# G-PiC_Door_Controller.net
KiCad netlist of a schematic drawn in EAGLE
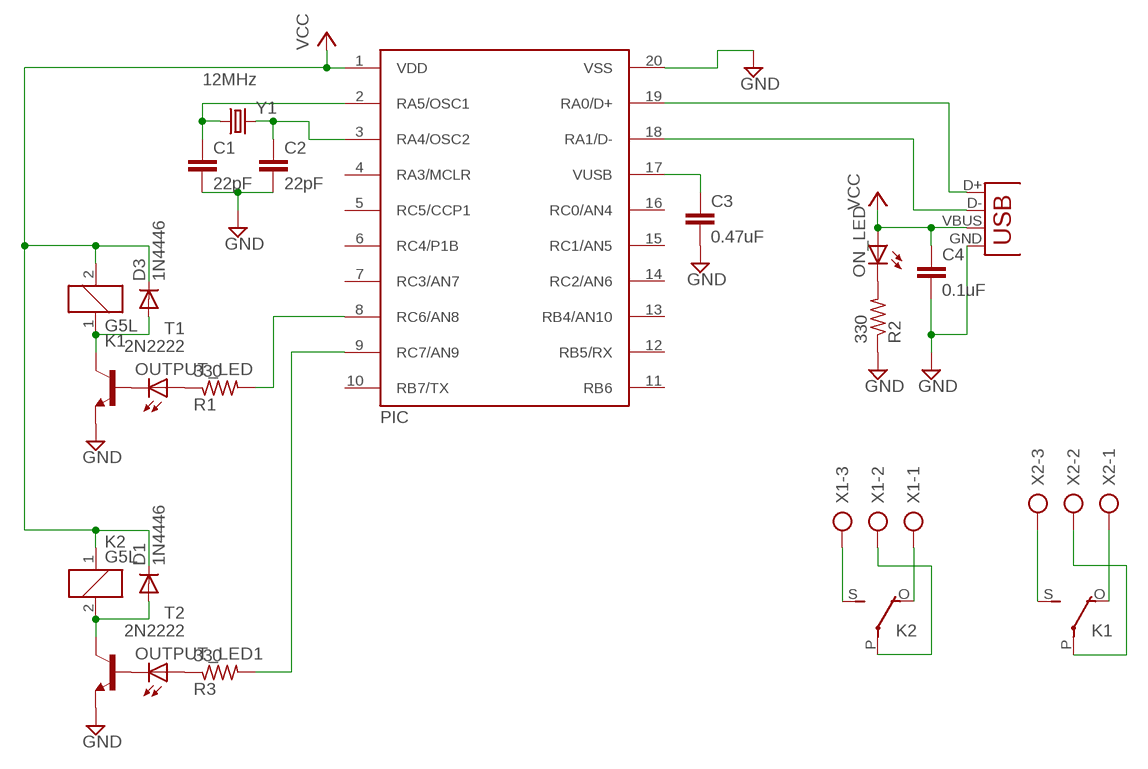
[diagram p0: schematic, sheet 1]

(export (version "E")
  (design (tool "Eeschema 10.0.6"))
  (components
    (comp (ref "C1")
      (value "22pF")
      (footprint "eagle-import:C5B3")
      (libsource (lib "eagle-import") (part "C5/3"))
    )
    (comp (ref "C2")
      (value "22pF")
      (footprint "eagle-import:C5B3")
      (libsource (lib "eagle-import") (part "C5/3"))
    )
    (comp (ref "C3")
      (value "0.47uF")
      (footprint "eagle-import:C5B3")
      (libsource (lib "eagle-import") (part "C5/3"))
    )
    (comp (ref "C4")
      (value "0.1uF")
      (footprint "eagle-import:C2.5-3")
      (libsource (lib "eagle-import") (part "C2,5-3"))
    )
    (comp (ref "D1")
      (value "1N4446")
      (footprint "eagle-import:DO35-10")
      (libsource (lib "eagle-import") (part "1N4446"))
    )
    (comp (ref "D3")
      (value "1N4446")
      (footprint "eagle-import:DO35-10")
      (libsource (lib "eagle-import") (part "1N4446"))
    )
    (comp (ref "K1")
      (value "G5L")
      (footprint "eagle-import:G5LE")
      (libsource (lib "eagle-import") (part "G5L"))
    )
    (comp (ref "K2")
      (value "G5L")
      (footprint "eagle-import:G5LE")
      (fields (field (name "OC_FARNELL") "unknown") (field (name "OC_NEWARK") "unknown"))
      (libsource (lib "eagle-import") (part "G5L"))
    )
    (comp (ref "ON_LED")
      (value "LED3MM")
      (footprint "eagle-import:LED3MM")
      (libsource (lib "eagle-import") (part "LED3MM"))
    )
    (comp (ref "OUTPUT_LED")
      (value "LED3MM")
      (footprint "eagle-import:LED3MM")
      (libsource (lib "eagle-import") (part "LED3MM"))
    )
    (comp (ref "OUTPUT_LED1")
      (value "LED3MM")
      (footprint "eagle-import:LED3MM")
      (libsource (lib "eagle-import") (part "LED3MM"))
    )
    (comp (ref "PIC")
      (value "PIC18F14K50")
      (footprint "eagle-import:DIL20")
      (libsource (lib "eagle-import") (part "PIC18F14K50"))
    )
    (comp (ref "R1")
      (value "330")
      (footprint "eagle-import:0204_7")
      (libsource (lib "eagle-import") (part "R-US_0204/7"))
    )
    (comp (ref "R2")
      (value "330")
      (footprint "eagle-import:0204_7")
      (libsource (lib "eagle-import") (part "R-US_0204/7"))
    )
    (comp (ref "R3")
      (value "330")
      (footprint "eagle-import:0204_7")
      (libsource (lib "eagle-import") (part "R-US_0204/7"))
    )
    (comp (ref "T1")
      (value "2N2222")
      (footprint "eagle-import:TO92-EBC-OVAL")
      (libsource (lib "eagle-import") (part "2N2222"))
    )
    (comp (ref "T2")
      (value "2N2222")
      (footprint "eagle-import:TO92-EBC-OVAL")
      (libsource (lib "eagle-import") (part "2N2222"))
    )
    (comp (ref "X1")
      (value "AK500/3-H")
      (footprint "eagle-import:AK500_3-H")
      (fields (field (name "OC_FARNELL") "unknown") (field (name "OC_NEWARK") "unknown"))
      (libsource (lib "eagle-import") (part "AK500/3-H"))
    )
    (comp (ref "X2")
      (value "AK500/3-H")
      (footprint "eagle-import:AK500_3-H")
      (libsource (lib "eagle-import") (part "AK500/3-H"))
    )
    (comp (ref "X3")
      (value "USBPTH")
      (footprint "eagle-import:USB-B-PTH")
      (libsource (lib "eagle-import") (part "USBPTH"))
    )
    (comp (ref "Y1")
      (value "12MHz")
      (footprint "eagle-import:HC49US")
      (libsource (lib "eagle-import") (part "CRYSTALHC49US"))
    )
  )
  (nets
    (net (code "1") (name "GND") (class "Default")
      (node (ref "C1") (pin "2") (pinfunction "2_2") (pintype "passive"))
      (node (ref "C2") (pin "2") (pinfunction "2_2") (pintype "passive"))
      (node (ref "C3") (pin "2") (pinfunction "2_2") (pintype "passive"))
      (node (ref "C4") (pin "2") (pinfunction "2_2") (pintype "passive"))
      (node (ref "PIC") (pin "20") (pinfunction "VSS_20") (pintype "bidirectional"))
      (node (ref "R2") (pin "1") (pinfunction "1_1") (pintype "passive"))
      (node (ref "T1") (pin "E") (pinfunction "E_E") (pintype "passive"))
      (node (ref "T2") (pin "E") (pinfunction "E_E") (pintype "passive"))
      (node (ref "X3") (pin "GND") (pinfunction "GND_GND") (pintype "bidirectional"))
    )
    (net (code "2") (name "Net-(D1-PadA)") (class "Default")
      (node (ref "D1") (pin "A") (pinfunction "A_A") (pintype "passive"))
      (node (ref "K2") (pin "2") (pinfunction "2_2") (pintype "passive"))
      (node (ref "T2") (pin "C") (pinfunction "C_C") (pintype "passive"))
    )
    (net (code "3") (name "Net-(D3-PadA)") (class "Default")
      (node (ref "D3") (pin "A") (pinfunction "A_A") (pintype "passive"))
      (node (ref "K1") (pin "1") (pinfunction "1_1") (pintype "passive"))
      (node (ref "T1") (pin "C") (pinfunction "C_C") (pintype "passive"))
    )
    (net (code "4") (name "Net-(ON_LED-C)") (class "Default")
      (node (ref "ON_LED") (pin "K") (pinfunction "C_K") (pintype "passive"))
      (node (ref "R2") (pin "2") (pinfunction "2_2") (pintype "passive"))
    )
    (net (code "5") (name "Net-(OUTPUT_LED-C)") (class "Default")
      (node (ref "OUTPUT_LED") (pin "K") (pinfunction "C_K") (pintype "passive"))
      (node (ref "T1") (pin "B") (pinfunction "B_B") (pintype "passive"))
    )
    (net (code "6") (name "Net-(OUTPUT_LED-PadA)") (class "Default")
      (node (ref "OUTPUT_LED") (pin "A") (pinfunction "A_A") (pintype "passive"))
      (node (ref "R1") (pin "1") (pinfunction "1_1") (pintype "passive"))
    )
    (net (code "7") (name "Net-(OUTPUT_LED1-C)") (class "Default")
      (node (ref "OUTPUT_LED1") (pin "K") (pinfunction "C_K") (pintype "passive"))
      (node (ref "T2") (pin "B") (pinfunction "B_B") (pintype "passive"))
    )
    (net (code "8") (name "Net-(OUTPUT_LED1-PadA)") (class "Default")
      (node (ref "OUTPUT_LED1") (pin "A") (pinfunction "A_A") (pintype "passive"))
      (node (ref "R3") (pin "1") (pinfunction "1_1") (pintype "passive"))
    )
    (net (code "9") (name "Net-(PIC-RA0{slash}D+)") (class "Default")
      (node (ref "PIC") (pin "19") (pinfunction "RA0/D+_19") (pintype "bidirectional"))
      (node (ref "X3") (pin "D+") (pinfunction "D+_D+") (pintype "bidirectional"))
    )
    (net (code "10") (name "Net-(PIC-RA1{slash}D-)") (class "Default")
      (node (ref "PIC") (pin "18") (pinfunction "RA1/D-_18") (pintype "bidirectional"))
      (node (ref "X3") (pin "D-") (pinfunction "D-_D-") (pintype "bidirectional"))
    )
    (net (code "11") (name "Net-(PIC-RA4{slash}OSC2)") (class "Default")
      (node (ref "C2") (pin "1") (pinfunction "1_1") (pintype "passive"))
      (node (ref "PIC") (pin "3") (pinfunction "RA4/OSC2_3") (pintype "bidirectional"))
      (node (ref "Y1") (pin "2") (pinfunction "2_2") (pintype "passive"))
    )
    (net (code "12") (name "Net-(PIC-RA5{slash}OSC1)") (class "Default")
      (node (ref "C1") (pin "1") (pinfunction "1_1") (pintype "passive"))
      (node (ref "PIC") (pin "2") (pinfunction "RA5/OSC1_2") (pintype "bidirectional"))
      (node (ref "Y1") (pin "1") (pinfunction "1_1") (pintype "passive"))
    )
    (net (code "13") (name "Net-(PIC-RC6{slash}AN8)") (class "Default")
      (node (ref "PIC") (pin "8") (pinfunction "RC6/AN8_8") (pintype "bidirectional"))
      (node (ref "R1") (pin "2") (pinfunction "2_2") (pintype "passive"))
    )
    (net (code "14") (name "Net-(PIC-RC7{slash}AN9)") (class "Default")
      (node (ref "PIC") (pin "9") (pinfunction "RC7/AN9_9") (pintype "bidirectional"))
      (node (ref "R3") (pin "2") (pinfunction "2_2") (pintype "passive"))
    )
    (net (code "15") (name "Net-(PIC-VUSB)") (class "Default")
      (node (ref "C3") (pin "1") (pinfunction "1_1") (pintype "passive"))
      (node (ref "PIC") (pin "17") (pinfunction "VUSB_17") (pintype "bidirectional"))
    )
    (net (code "16") (name "Net-(X1A-KL)") (class "Default")
      (node (ref "K2") (pin "O") (pinfunction "O_O") (pintype "passive"))
      (node (ref "X1") (pin "1") (pinfunction "KL_1") (pintype "passive"))
    )
    (net (code "17") (name "Net-(X1B-KL)") (class "Default")
      (node (ref "K2") (pin "P") (pinfunction "P_P") (pintype "passive"))
      (node (ref "X1") (pin "2") (pinfunction "KL_2") (pintype "passive"))
    )
    (net (code "18") (name "Net-(X1C-KL)") (class "Default")
      (node (ref "K2") (pin "S") (pinfunction "S_S") (pintype "passive"))
      (node (ref "X1") (pin "3") (pinfunction "KL_3") (pintype "passive"))
    )
    (net (code "19") (name "Net-(X2A-KL)") (class "Default")
      (node (ref "K1") (pin "O") (pinfunction "O_O") (pintype "passive"))
      (node (ref "X2") (pin "1") (pinfunction "KL_1") (pintype "passive"))
    )
    (net (code "20") (name "Net-(X2B-KL)") (class "Default")
      (node (ref "K1") (pin "P") (pinfunction "P_P") (pintype "passive"))
      (node (ref "X2") (pin "2") (pinfunction "KL_2") (pintype "passive"))
    )
    (net (code "21") (name "Net-(X2C-KL)") (class "Default")
      (node (ref "K1") (pin "S") (pinfunction "S_S") (pintype "passive"))
      (node (ref "X2") (pin "3") (pinfunction "KL_3") (pintype "passive"))
    )
    (net (code "22") (name "VCC") (class "Default")
      (node (ref "C4") (pin "1") (pinfunction "1_1") (pintype "passive"))
      (node (ref "D1") (pin "C") (pinfunction "C_C") (pintype "passive"))
      (node (ref "D3") (pin "C") (pinfunction "C_C") (pintype "passive"))
      (node (ref "K1") (pin "2") (pinfunction "2_2") (pintype "passive"))
      (node (ref "K2") (pin "1") (pinfunction "1_1") (pintype "passive"))
      (node (ref "ON_LED") (pin "A") (pinfunction "A_A") (pintype "passive"))
      (node (ref "PIC") (pin "1") (pinfunction "VDD_1") (pintype "bidirectional"))
      (node (ref "X3") (pin "VBUS") (pinfunction "VBUS_VBUS") (pintype "bidirectional"))
    )
    (net (code "23") (name "unconnected-(PIC-RA3{slash}MCLR-Pad4)") (class "Default")
      (node (ref "PIC") (pin "4") (pinfunction "RA3/MCLR_4") (pintype "bidirectional"))
    )
    (net (code "24") (name "unconnected-(PIC-RB4{slash}AN10-Pad13)") (class "Default")
      (node (ref "PIC") (pin "13") (pinfunction "RB4/AN10_13") (pintype "bidirectional"))
    )
    (net (code "25") (name "unconnected-(PIC-RB5{slash}RX-Pad12)") (class "Default")
      (node (ref "PIC") (pin "12") (pinfunction "RB5/RX_12") (pintype "bidirectional"))
    )
    (net (code "26") (name "unconnected-(PIC-RB6-Pad11)") (class "Default")
      (node (ref "PIC") (pin "11") (pinfunction "RB6_11") (pintype "bidirectional"))
    )
    (net (code "27") (name "unconnected-(PIC-RB7{slash}TX-Pad10)") (class "Default")
      (node (ref "PIC") (pin "10") (pinfunction "RB7/TX_10") (pintype "bidirectional"))
    )
    (net (code "28") (name "unconnected-(PIC-RC0{slash}AN4-Pad16)") (class "Default")
      (node (ref "PIC") (pin "16") (pinfunction "RC0/AN4_16") (pintype "bidirectional"))
    )
    (net (code "29") (name "unconnected-(PIC-RC1{slash}AN5-Pad15)") (class "Default")
      (node (ref "PIC") (pin "15") (pinfunction "RC1/AN5_15") (pintype "bidirectional"))
    )
    (net (code "30") (name "unconnected-(PIC-RC2{slash}AN6-Pad14)") (class "Default")
      (node (ref "PIC") (pin "14") (pinfunction "RC2/AN6_14") (pintype "bidirectional"))
    )
    (net (code "31") (name "unconnected-(PIC-RC3{slash}AN7-Pad7)") (class "Default")
      (node (ref "PIC") (pin "7") (pinfunction "RC3/AN7_7") (pintype "bidirectional"))
    )
    (net (code "32") (name "unconnected-(PIC-RC4{slash}P1B-Pad6)") (class "Default")
      (node (ref "PIC") (pin "6") (pinfunction "RC4/P1B_6") (pintype "bidirectional"))
    )
    (net (code "33") (name "unconnected-(PIC-RC5{slash}CCP1-Pad5)") (class "Default")
      (node (ref "PIC") (pin "5") (pinfunction "RC5/CCP1_5") (pintype "bidirectional"))
    )
  )
)
